# PCIe_USB30_Power.net
KiCad netlist of a schematic drawn in Altium Designer
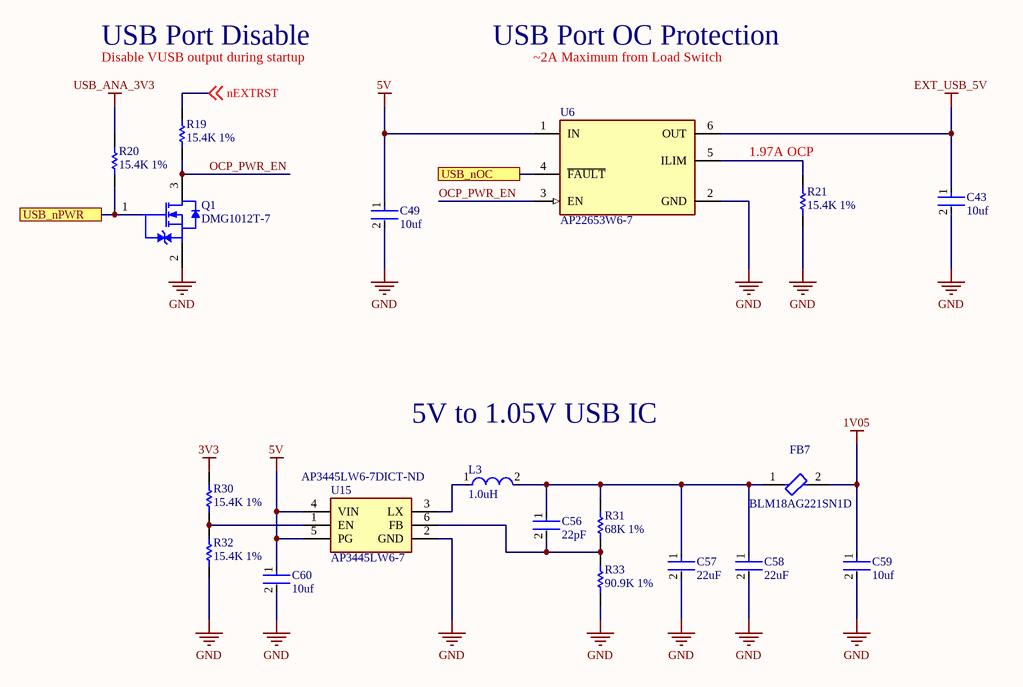
[diagram p0: PCIe_USB30_Power.SchDoc]

(export (version "E")
  (design (tool "Eeschema 10.0.6"))
  (components
    (comp (ref "C43")
      (value "10uf")
      (footprint "FP-GRM188-0_2-IPC_C")
      (description "Chip Multilayer Ceramic Capacitors for General Purpose, 0603, 10uF, X5R, 15%, 20%, 35V")
      (fields (field (name "TOLERANCE") "20%"))
      (libsource (lib "Altium Content Vault") (part "11868f565c42a9108669ba33697ecf6"))
    )
    (comp (ref "C49")
      (value "10uf")
      (footprint "FP-GRM188-0_2-IPC_C")
      (description "Chip Multilayer Ceramic Capacitors for General Purpose, 0603, 10uF, X5R, 15%, 20%, 35V")
      (fields (field (name "TOLERANCE") "20%"))
      (libsource (lib "Altium Content Vault") (part "11868f565c42a9108669ba33697ecf6"))
    )
    (comp (ref "C56")
      (value "22pF")
      (footprint "FP-C0603C-CF-MFG")
      (description "CAP CER 22PF 50V NP0 0603")
      (fields
        (field (name "OCTOPART") "https://octopart.com/c0603c220d5gactu-kemet-9143734")
        (field (name "TOLERANCE") "0.5 pF")
      )
      (libsource (lib "Altium Content Vault") (part "b4654b650e69147ec39a6b967a45e02"))
    )
    (comp (ref "C57")
      (value "22uF")
      (footprint "FP-GRM21B-0_15-MFG")
      (description "Chip Multilayer Ceramic Capacitors for General Purpose, 0805, 22uF, X5R, 15%, 20%, 6.3V")
      (fields (field (name "VOLTAGE") "6.3V") (field (name "TOLERANCE") "20%"))
      (libsource (lib "Altium Content Vault") (part "b4654b650e69147ec39a6b967a45e02"))
    )
    (comp (ref "C58")
      (value "22uF")
      (footprint "FP-GRM21B-0_15-MFG")
      (description "Chip Multilayer Ceramic Capacitors for General Purpose, 0805, 22uF, X5R, 15%, 20%, 6.3V")
      (fields (field (name "VOLTAGE") "6.3V") (field (name "TOLERANCE") "20%"))
      (libsource (lib "Altium Content Vault") (part "b4654b650e69147ec39a6b967a45e02"))
    )
    (comp (ref "C59")
      (value "10uf")
      (footprint "FP-GRM188-0_2-IPC_C")
      (description "Chip Multilayer Ceramic Capacitors for General Purpose, 0603, 10uF, X5R, 15%, 20%, 35V")
      (fields (field (name "TOLERANCE") "20%"))
      (libsource (lib "Altium Content Vault") (part "11868f565c42a9108669ba33697ecf6"))
    )
    (comp (ref "C60")
      (value "10uf")
      (footprint "FP-GRM188-0_2-IPC_C")
      (description "Chip Multilayer Ceramic Capacitors for General Purpose, 0603, 10uF, X5R, 15%, 20%, 35V")
      (fields (field (name "TOLERANCE") "20%"))
      (libsource (lib "Altium Content Vault") (part "11868f565c42a9108669ba33697ecf6"))
    )
    (comp (ref "FB7")
      (value "BLM18AG221SN1D")
      (footprint "FP-BLM18-0_15-t0_8-IPC_A")
      (description "Chip Ferrite Bead, 0603, 220Ω @ 100MHz, 0.25Ω, 25%, 700mA")
      (fields (field (name "TOLERANCE") "25%"))
      (libsource (lib "Altium Content Vault") (part "5f30dd21d616792df468990f7003faa"))
    )
    (comp (ref "L3")
      (value "1.0uH")
      (footprint "FP-NR4018-MFG")
      (description "SMD Power Inductors for Automotive Applications 1.0uH ±30% 3.2A 32.4mΩ")
      (fields (field (name "TOLERANCE") "30%"))
      (libsource (lib "Altium Content Vault") (part "725321dda6339637d4d059423bc1c3c"))
    )
    (comp (ref "Q1")
      (value "DMG1012T-7")
      (footprint "DIOD-SOT523-3_V")
      (description "N-Channel Enhancement Mode MOSFET, 20 V, 630 mA, -55 to 150 degC, 3-Pin SOT23, RoHS, Tape and Reel")
      (fields (field (name "MANUFACTURER") "Diodes Inc"))
      (libsource (lib "Altium Content Vault") (part "NEMOS-GSD-3_E"))
    )
    (comp (ref "R19")
      (value "15.4K 1%")
      (footprint "RESC1005X40X25ML05T10")
      (fields (field (name "PART NUMBER") "RC0402FR-0715K4L") (field (name "MANUFACTURER") "Yageo"))
      (libsource (lib "Altium Content Vault") (part "RES"))
    )
    (comp (ref "R20")
      (value "15.4K 1%")
      (footprint "RESC1005X40X25ML05T10")
      (fields (field (name "PART NUMBER") "RC0402FR-0715K4L") (field (name "MANUFACTURER") "Yageo"))
      (libsource (lib "Altium Content Vault") (part "RES"))
    )
    (comp (ref "R21")
      (value "15.4K 1%")
      (footprint "RESC1005X40X25ML05T10")
      (fields (field (name "PART NUMBER") "RC0402FR-0715K4L") (field (name "MANUFACTURER") "Yageo"))
      (libsource (lib "Altium Content Vault") (part "RES"))
    )
    (comp (ref "R30")
      (value "15.4K 1%")
      (footprint "RESC1005X40X25ML05T10")
      (fields (field (name "PART NUMBER") "RC0402FR-0715K4L") (field (name "MANUFACTURER") "Yageo"))
      (libsource (lib "Altium Content Vault") (part "RES"))
    )
    (comp (ref "R31")
      (value "68K 1%")
      (footprint "RESC1005X40X25ML05T05")
      (fields (field (name "PART NUMBER") "ERJ2RKF6802X") (field (name "MANUFACTURER") "Panasonic"))
      (libsource (lib "Altium Content Vault") (part "RES"))
    )
    (comp (ref "R32")
      (value "15.4K 1%")
      (footprint "RESC1005X40X25ML05T10")
      (fields (field (name "PART NUMBER") "RC0402FR-0715K4L") (field (name "MANUFACTURER") "Yageo"))
      (libsource (lib "Altium Content Vault") (part "RES"))
    )
    (comp (ref "R33")
      (value "90.9K 1%")
      (footprint "RESC1005X40X25NL05T10")
      (fields (field (name "MANUFACTURER") "Yageo") (field (name "PART NUMBER") "RC0402FR-0790K9L"))
      (libsource (lib "Altium Content Vault") (part "RES"))
    )
    (comp (ref "U6")
      (value "AP22653W6-7")
      (footprint "FP-SOT26-MFG")
      (description "LOAD SWITCH,SOT26,T&R,3K")
      (libsource (lib "Altium Content Vault") (part "bad2b8b447a47ab10bab651f807ccff"))
    )
    (comp (ref "U15")
      (value "AP3445LW6-7")
      (footprint "SamacSys:SOT95P285X140-6N")
      (description "Integrated Circuit")
      (fields
        (field (name "MOUSER PART NUMBER") "621-AP3445LW6-7")
        (field (name "SUPPLIER PART NUMBER 1") "AP3445LW6-7DICT-ND")
      )
      (libsource (lib "*") (part "AP3445LW6-7"))
    )
  )
  (nets
    (net (code "1") (name "/OCP_PWR_EN") (class "Default")
      (node (ref "Q1") (pin "3") (pinfunction "D_3") (pintype "passive"))
      (node (ref "R19") (pin "1") (pinfunction "1_1") (pintype "passive"))
      (node (ref "U6") (pin "3") (pinfunction "EN_3") (pintype "input"))
    )
    (net (code "2") (name "/USB_nOC") (class "Default")
      (node (ref "U6") (pin "4") (pinfunction "~{FAULT}_4") (pintype "open_collector"))
    )
    (net (code "3") (name "/USB_nPWR") (class "Default")
      (node (ref "Q1") (pin "1") (pinfunction "G_1") (pintype "passive"))
      (node (ref "R20") (pin "1") (pinfunction "1_1") (pintype "passive"))
    )
    (net (code "4") (name "1V05") (class "Default")
      (node (ref "C59") (pin "1") (pinfunction "1_1") (pintype "passive"))
      (node (ref "FB7") (pin "2") (pinfunction "2_2") (pintype "passive"))
    )
    (net (code "5") (name "3V3") (class "Default")
      (node (ref "R30") (pin "2") (pinfunction "2_2") (pintype "passive"))
    )
    (net (code "6") (name "5V") (class "Default")
      (node (ref "C49") (pin "1") (pinfunction "1_1") (pintype "passive"))
      (node (ref "C60") (pin "1") (pinfunction "1_1") (pintype "passive"))
      (node (ref "U15") (pin "4") (pinfunction "VIN_4") (pintype "passive"))
      (node (ref "U15") (pin "5") (pinfunction "PG_5") (pintype "passive"))
      (node (ref "U6") (pin "1") (pinfunction "IN_1") (pintype "power_in"))
    )
    (net (code "7") (name "EXT_USB_5V") (class "Default")
      (node (ref "C43") (pin "1") (pinfunction "1_1") (pintype "passive"))
      (node (ref "U6") (pin "6") (pinfunction "OUT_6") (pintype "passive"))
    )
    (net (code "8") (name "GND") (class "Default")
      (node (ref "C43") (pin "2") (pinfunction "2_2") (pintype "passive"))
      (node (ref "C49") (pin "2") (pinfunction "2_2") (pintype "passive"))
      (node (ref "C57") (pin "2") (pinfunction "2_2") (pintype "passive"))
      (node (ref "C58") (pin "2") (pinfunction "2_2") (pintype "passive"))
      (node (ref "C59") (pin "2") (pinfunction "2_2") (pintype "passive"))
      (node (ref "C60") (pin "2") (pinfunction "2_2") (pintype "passive"))
      (node (ref "Q1") (pin "2") (pinfunction "S_2") (pintype "passive"))
      (node (ref "R21") (pin "1") (pinfunction "1_1") (pintype "passive"))
      (node (ref "R32") (pin "1") (pinfunction "1_1") (pintype "passive"))
      (node (ref "R33") (pin "1") (pinfunction "1_1") (pintype "passive"))
      (node (ref "U15") (pin "2") (pinfunction "GND_2") (pintype "passive"))
      (node (ref "U6") (pin "2") (pinfunction "GND_2") (pintype "power_in"))
    )
    (net (code "9") (name "Net-(C56-Pad1)") (class "Default")
      (node (ref "C56") (pin "1") (pinfunction "1_1") (pintype "passive"))
      (node (ref "C57") (pin "1") (pinfunction "1_1") (pintype "passive"))
      (node (ref "C58") (pin "1") (pinfunction "1_1") (pintype "passive"))
      (node (ref "FB7") (pin "1") (pinfunction "1_1") (pintype "passive"))
      (node (ref "L3") (pin "2") (pinfunction "2_2") (pintype "passive"))
      (node (ref "R31") (pin "1") (pinfunction "1_1") (pintype "passive"))
    )
    (net (code "10") (name "Net-(U6-ILIM)") (class "Default")
      (node (ref "R21") (pin "2") (pinfunction "2_2") (pintype "passive"))
      (node (ref "U6") (pin "5") (pinfunction "ILIM_5") (pintype "passive"))
    )
    (net (code "11") (name "Net-(U15-EN)") (class "Default")
      (node (ref "R30") (pin "1") (pinfunction "1_1") (pintype "passive"))
      (node (ref "R32") (pin "2") (pinfunction "2_2") (pintype "passive"))
      (node (ref "U15") (pin "1") (pinfunction "EN_1") (pintype "passive"))
    )
    (net (code "12") (name "Net-(U15-FB)") (class "Default")
      (node (ref "C56") (pin "2") (pinfunction "2_2") (pintype "passive"))
      (node (ref "R31") (pin "2") (pinfunction "2_2") (pintype "passive"))
      (node (ref "R33") (pin "2") (pinfunction "2_2") (pintype "passive"))
      (node (ref "U15") (pin "6") (pinfunction "FB_6") (pintype "passive"))
    )
    (net (code "13") (name "Net-(U15-LX)") (class "Default")
      (node (ref "L3") (pin "1") (pinfunction "1_1") (pintype "passive"))
      (node (ref "U15") (pin "3") (pinfunction "LX_3") (pintype "passive"))
    )
    (net (code "14") (name "USB_ANA_3V3") (class "Default")
      (node (ref "R20") (pin "2") (pinfunction "2_2") (pintype "passive"))
    )
    (net (code "15") (name "nEXTRST") (class "Default")
      (node (ref "R19") (pin "2") (pinfunction "2_2") (pintype "passive"))
    )
  )
)
